# Ultra96toPMODV10.net
KiCad netlist of a schematic drawn in EAGLE
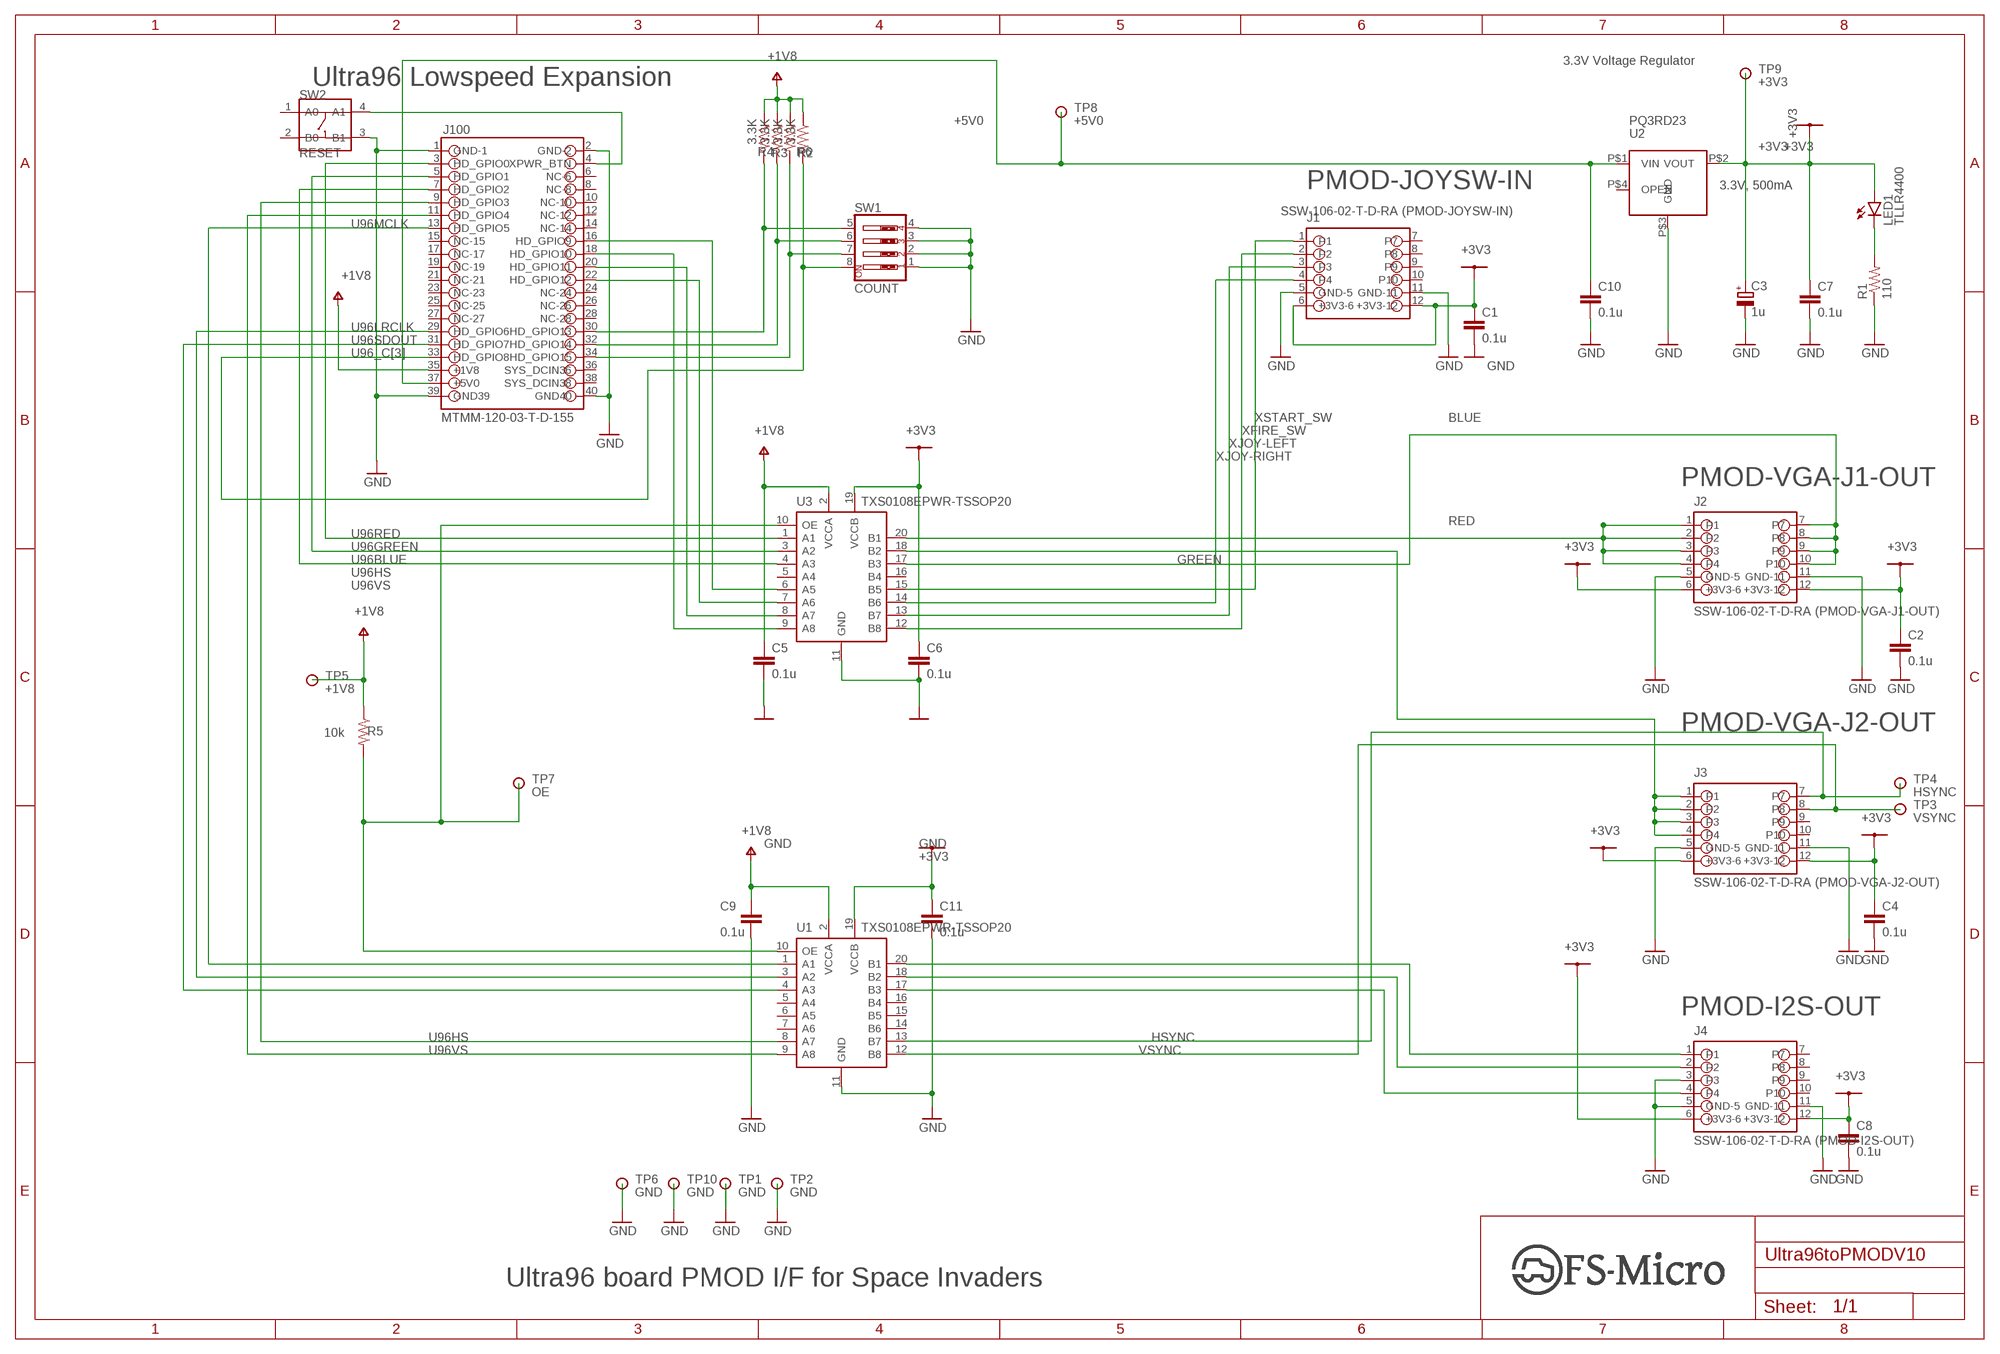
[diagram p0: schematic, sheet 1]

(export (version "E")
  (design (tool "Eeschema 10.0.6"))
  (components
    (comp (ref "C1")
      (value "0.1u")
      (footprint "eagle-import:C050-025X075")
      (libsource (lib "eagle-import") (part "C-EU050-025X075"))
    )
    (comp (ref "C2")
      (value "0.1u")
      (footprint "eagle-import:C050-025X075")
      (libsource (lib "eagle-import") (part "C-EU050-025X075"))
    )
    (comp (ref "C3")
      (value "1u")
      (footprint "eagle-import:E2,5-5")
      (libsource (lib "eagle-import") (part "CPOL-EUE2.5-5"))
    )
    (comp (ref "C4")
      (value "0.1u")
      (footprint "eagle-import:C050-025X075")
      (libsource (lib "eagle-import") (part "C-EU050-025X075"))
    )
    (comp (ref "C5")
      (value "0.1u")
      (footprint "eagle-import:C050-025X075")
      (libsource (lib "eagle-import") (part "C-EU050-025X075"))
    )
    (comp (ref "C6")
      (value "0.1u")
      (footprint "eagle-import:C050-025X075")
      (libsource (lib "eagle-import") (part "C-EU050-025X075"))
    )
    (comp (ref "C7")
      (value "0.1u")
      (footprint "eagle-import:C050-025X075")
      (libsource (lib "eagle-import") (part "C-EU050-025X075"))
    )
    (comp (ref "C8")
      (value "0.1u")
      (footprint "eagle-import:C050-025X075")
      (libsource (lib "eagle-import") (part "C-EU050-025X075"))
    )
    (comp (ref "C9")
      (value "0.1u")
      (footprint "eagle-import:C050-025X075")
      (libsource (lib "eagle-import") (part "C-EU050-025X075"))
    )
    (comp (ref "C10")
      (value "0.1u")
      (footprint "eagle-import:C050-025X075")
      (libsource (lib "eagle-import") (part "C-EU050-025X075"))
    )
    (comp (ref "C11")
      (value "0.1u")
      (footprint "eagle-import:C050-025X075")
      (libsource (lib "eagle-import") (part "C-EU050-025X075"))
    )
    (comp (ref "J1")
      (value "SSW-106-02-T-D-RA (PMOD-JOYSW-IN)")
      (footprint "eagle-import:SSW-106-02-T-D-RA")
      (libsource (lib "eagle-import") (part "SSW-106-02-T-D-RA"))
    )
    (comp (ref "J2")
      (value "SSW-106-02-T-D-RA (PMOD-VGA-J1-OUT)")
      (footprint "eagle-import:SSW-106-02-T-D-RA")
      (libsource (lib "eagle-import") (part "SSW-106-02-T-D-RA"))
    )
    (comp (ref "J3")
      (value "SSW-106-02-T-D-RA (PMOD-VGA-J2-OUT)")
      (footprint "eagle-import:SSW-106-02-T-D-RA")
      (libsource (lib "eagle-import") (part "SSW-106-02-T-D-RA"))
    )
    (comp (ref "J4")
      (value "SSW-106-02-T-D-RA (PMOD-I2S-OUT)")
      (footprint "eagle-import:SSW-106-02-T-D-RA")
      (libsource (lib "eagle-import") (part "SSW-106-02-T-D-RA"))
    )
    (comp (ref "J100")
      (value "MTMM-120-03-T-D-155")
      (footprint "eagle-import:MTMM-120-03-T-D-155")
      (libsource (lib "eagle-import") (part "MTMM-120-03-T-D-155"))
    )
    (comp (ref "LED1")
      (value "TLLR4400")
      (footprint "eagle-import:LED3MM")
      (fields (field (name "MF") "VISHAY SEMICONDUCTOR"))
      (libsource (lib "eagle-import") (part "TLLR4400"))
    )
    (comp (ref "R1")
      (value "110")
      (footprint "eagle-import:0207_10")
      (libsource (lib "eagle-import") (part "R-US_0207/10"))
    )
    (comp (ref "R2")
      (value "3.3K")
      (footprint "eagle-import:0207_10")
      (libsource (lib "eagle-import") (part "R-US_0207/10"))
    )
    (comp (ref "R3")
      (value "3.3K")
      (footprint "eagle-import:0207_10")
      (libsource (lib "eagle-import") (part "R-US_0207/10"))
    )
    (comp (ref "R4")
      (value "3.3K")
      (footprint "eagle-import:0207_10")
      (libsource (lib "eagle-import") (part "R-US_0207/10"))
    )
    (comp (ref "R5")
      (value "10k")
      (footprint "eagle-import:0207_10")
      (libsource (lib "eagle-import") (part "R-US_0207/10"))
    )
    (comp (ref "R6")
      (value "3.3K")
      (footprint "eagle-import:0207_10")
      (libsource (lib "eagle-import") (part "R-US_0207/10"))
    )
    (comp (ref "SW1")
      (value "COUNT")
      (footprint "eagle-import:EDG-04")
      (libsource (lib "eagle-import") (part "SW_DIP-4"))
    )
    (comp (ref "SW2")
      (value "RESET")
      (footprint "eagle-import:SW4-6.0X6.0X5.0MM")
      (libsource (lib "eagle-import") (part "DIP-SWITCH-TACTILE-SPST-NO/TS-1109(4P-D6.0MM)'TS-1109'"))
    )
    (comp (ref "TP1")
      (value "GND")
      (footprint "eagle-import:TP")
      (libsource (lib "eagle-import") (part "TP"))
    )
    (comp (ref "TP2")
      (value "GND")
      (footprint "eagle-import:TP")
      (libsource (lib "eagle-import") (part "TP"))
    )
    (comp (ref "TP3")
      (value "VSYNC")
      (footprint "eagle-import:TP")
      (libsource (lib "eagle-import") (part "TP"))
    )
    (comp (ref "TP4")
      (value "HSYNC")
      (footprint "eagle-import:TP")
      (libsource (lib "eagle-import") (part "TP"))
    )
    (comp (ref "TP5")
      (value "+1V8")
      (footprint "eagle-import:TP")
      (libsource (lib "eagle-import") (part "TP"))
    )
    (comp (ref "TP6")
      (value "GND")
      (footprint "eagle-import:TP")
      (libsource (lib "eagle-import") (part "TP"))
    )
    (comp (ref "TP7") (value "OE") (footprint "eagle-import:TP") (libsource (lib "eagle-import") (part "TP")))
    (comp (ref "TP8")
      (value "+5V0")
      (footprint "eagle-import:TP")
      (libsource (lib "eagle-import") (part "TP"))
    )
    (comp (ref "TP9")
      (value "+3V3")
      (footprint "eagle-import:TP")
      (libsource (lib "eagle-import") (part "TP"))
    )
    (comp (ref "TP10")
      (value "GND")
      (footprint "eagle-import:TP")
      (libsource (lib "eagle-import") (part "TP"))
    )
    (comp (ref "U1")
      (value "TXS0108EPWR-TSSOP20")
      (footprint "eagle-import:TSSOP20-0.65-6.5X4.4MM")
      (fields (field (name "MPN") "TXS0108EPWR"))
      (libsource (lib "eagle-import") (part "LOGIC-TXS0108EPWR(TSSOP20)"))
    )
    (comp (ref "U2")
      (value "PQ3RD23")
      (footprint "eagle-import:PQ3RD23")
      (libsource (lib "eagle-import") (part "PQ3RD23"))
    )
    (comp (ref "U3")
      (value "TXS0108EPWR-TSSOP20")
      (footprint "eagle-import:TSSOP20-0.65-6.5X4.4MM")
      (fields (field (name "MPN") "TXS0108EPWR"))
      (libsource (lib "eagle-import") (part "LOGIC-TXS0108EPWR(TSSOP20)"))
    )
  )
  (nets
    (net (code "1") (name "+1V8") (class "Default")
      (node (ref "C5") (pin "1") (pinfunction "1_1") (pintype "passive"))
      (node (ref "C9") (pin "1") (pinfunction "1_1") (pintype "passive"))
      (node (ref "J100") (pin "35") (pinfunction "+1V8_35") (pintype "passive"))
      (node (ref "R2") (pin "1") (pinfunction "1_1") (pintype "passive"))
      (node (ref "R3") (pin "1") (pinfunction "1_1") (pintype "passive"))
      (node (ref "R4") (pin "1") (pinfunction "1_1") (pintype "passive"))
      (node (ref "R5") (pin "1") (pinfunction "1_1") (pintype "passive"))
      (node (ref "R6") (pin "1") (pinfunction "1_1") (pintype "passive"))
      (node (ref "TP5") (pin "P$1") (pinfunction "P$1_P$1") (pintype "bidirectional"))
      (node (ref "U1") (pin "2") (pinfunction "VCCA_2") (pintype "bidirectional"))
      (node (ref "U3") (pin "2") (pinfunction "VCCA_2") (pintype "bidirectional"))
    )
    (net (code "2") (name "+3V3") (class "Default")
      (node (ref "C1") (pin "1") (pinfunction "1_1") (pintype "passive"))
      (node (ref "C11") (pin "1") (pinfunction "1_1") (pintype "passive"))
      (node (ref "C2") (pin "1") (pinfunction "1_1") (pintype "passive"))
      (node (ref "C3") (pin "+") (pinfunction "+_+") (pintype "passive"))
      (node (ref "C4") (pin "1") (pinfunction "1_1") (pintype "passive"))
      (node (ref "C6") (pin "1") (pinfunction "1_1") (pintype "passive"))
      (node (ref "C7") (pin "1") (pinfunction "1_1") (pintype "passive"))
      (node (ref "C8") (pin "1") (pinfunction "1_1") (pintype "passive"))
      (node (ref "J1") (pin "12") (pinfunction "+3V3-12_12") (pintype "passive"))
      (node (ref "J1") (pin "6") (pinfunction "+3V3-6_6") (pintype "passive"))
      (node (ref "J2") (pin "12") (pinfunction "+3V3-12_12") (pintype "passive"))
      (node (ref "J2") (pin "6") (pinfunction "+3V3-6_6") (pintype "passive"))
      (node (ref "J3") (pin "12") (pinfunction "+3V3-12_12") (pintype "passive"))
      (node (ref "J3") (pin "6") (pinfunction "+3V3-6_6") (pintype "passive"))
      (node (ref "J4") (pin "12") (pinfunction "+3V3-12_12") (pintype "passive"))
      (node (ref "J4") (pin "6") (pinfunction "+3V3-6_6") (pintype "passive"))
      (node (ref "LED1") (pin "A") (pinfunction "A_A") (pintype "passive"))
      (node (ref "TP9") (pin "P$1") (pinfunction "P$1_P$1") (pintype "bidirectional"))
      (node (ref "U1") (pin "19") (pinfunction "VCCB_19") (pintype "bidirectional"))
      (node (ref "U2") (pin "P$2") (pinfunction "VOUT_P$2") (pintype "passive"))
      (node (ref "U3") (pin "19") (pinfunction "VCCB_19") (pintype "bidirectional"))
    )
    (net (code "3") (name "/+5V0") (class "Default")
      (node (ref "C10") (pin "1") (pinfunction "1_1") (pintype "passive"))
      (node (ref "J100") (pin "37") (pinfunction "+5V0_37") (pintype "passive"))
      (node (ref "TP8") (pin "P$1") (pinfunction "P$1_P$1") (pintype "bidirectional"))
      (node (ref "U2") (pin "P$1") (pinfunction "VIN_P$1") (pintype "passive"))
    )
    (net (code "4") (name "/BLUE") (class "Default")
      (node (ref "J2") (pin "10") (pinfunction "P10_10") (pintype "bidirectional"))
      (node (ref "J2") (pin "7") (pinfunction "P7_7") (pintype "bidirectional"))
      (node (ref "J2") (pin "8") (pinfunction "P8_8") (pintype "bidirectional"))
      (node (ref "J2") (pin "9") (pinfunction "P9_9") (pintype "bidirectional"))
      (node (ref "U3") (pin "17") (pinfunction "B3_17") (pintype "bidirectional"))
    )
    (net (code "5") (name "/GREEN") (class "Default")
      (node (ref "J3") (pin "1") (pinfunction "P1_1") (pintype "input"))
      (node (ref "J3") (pin "2") (pinfunction "P2_2") (pintype "bidirectional"))
      (node (ref "J3") (pin "3") (pinfunction "P3_3") (pintype "bidirectional"))
      (node (ref "J3") (pin "4") (pinfunction "P4_4") (pintype "bidirectional"))
      (node (ref "U3") (pin "18") (pinfunction "B2_18") (pintype "bidirectional"))
    )
    (net (code "6") (name "/HSYNC") (class "Default")
      (node (ref "J3") (pin "7") (pinfunction "P7_7") (pintype "bidirectional"))
      (node (ref "TP4") (pin "P$1") (pinfunction "P$1_P$1") (pintype "bidirectional"))
      (node (ref "U1") (pin "13") (pinfunction "B7_13") (pintype "bidirectional"))
    )
    (net (code "7") (name "/RED") (class "Default")
      (node (ref "J2") (pin "1") (pinfunction "P1_1") (pintype "input"))
      (node (ref "J2") (pin "2") (pinfunction "P2_2") (pintype "bidirectional"))
      (node (ref "J2") (pin "3") (pinfunction "P3_3") (pintype "bidirectional"))
      (node (ref "J2") (pin "4") (pinfunction "P4_4") (pintype "bidirectional"))
      (node (ref "U3") (pin "20") (pinfunction "B1_20") (pintype "bidirectional"))
    )
    (net (code "8") (name "/U96BLUE") (class "Default")
      (node (ref "J100") (pin "7") (pinfunction "HD_GPIO2_7") (pintype "bidirectional"))
      (node (ref "U3") (pin "4") (pinfunction "A3_4") (pintype "bidirectional"))
    )
    (net (code "9") (name "/U96GREEN") (class "Default")
      (node (ref "J100") (pin "5") (pinfunction "HD_GPIO1_5") (pintype "bidirectional"))
      (node (ref "U3") (pin "3") (pinfunction "A2_3") (pintype "bidirectional"))
    )
    (net (code "10") (name "/U96HS") (class "Default")
      (node (ref "J100") (pin "9") (pinfunction "HD_GPIO3_9") (pintype "bidirectional"))
      (node (ref "U1") (pin "8") (pinfunction "A7_8") (pintype "bidirectional"))
    )
    (net (code "11") (name "/U96LRCLK") (class "Default")
      (node (ref "J100") (pin "29") (pinfunction "HD_GPIO6_29") (pintype "bidirectional"))
      (node (ref "U1") (pin "3") (pinfunction "A2_3") (pintype "bidirectional"))
    )
    (net (code "12") (name "/U96MCLK") (class "Default")
      (node (ref "J100") (pin "13") (pinfunction "HD_GPIO5_13") (pintype "bidirectional"))
      (node (ref "U1") (pin "1") (pinfunction "A1_1") (pintype "bidirectional"))
    )
    (net (code "13") (name "/U96RED") (class "Default")
      (node (ref "J100") (pin "3") (pinfunction "HD_GPIO0_3") (pintype "bidirectional"))
      (node (ref "U3") (pin "1") (pinfunction "A1_1") (pintype "bidirectional"))
    )
    (net (code "14") (name "/U96SDOUT") (class "Default")
      (node (ref "J100") (pin "31") (pinfunction "HD_GPIO7_31") (pintype "bidirectional"))
      (node (ref "U1") (pin "4") (pinfunction "A3_4") (pintype "bidirectional"))
    )
    (net (code "15") (name "/U96VS") (class "Default")
      (node (ref "J100") (pin "11") (pinfunction "HD_GPIO4_11") (pintype "bidirectional"))
      (node (ref "U1") (pin "9") (pinfunction "A8_9") (pintype "bidirectional"))
    )
    (net (code "16") (name "/U96_C[3]") (class "Default")
      (node (ref "J100") (pin "33") (pinfunction "HD_GPIO8_33") (pintype "bidirectional"))
      (node (ref "R6") (pin "2") (pinfunction "2_2") (pintype "passive"))
      (node (ref "SW1") (pin "8") (pinfunction "8_8") (pintype "passive"))
    )
    (net (code "17") (name "/VSYNC") (class "Default")
      (node (ref "J3") (pin "8") (pinfunction "P8_8") (pintype "bidirectional"))
      (node (ref "TP3") (pin "P$1") (pinfunction "P$1_P$1") (pintype "bidirectional"))
      (node (ref "U1") (pin "12") (pinfunction "B8_12") (pintype "bidirectional"))
    )
    (net (code "18") (name "/XFIRE_SW") (class "Default")
      (node (ref "J1") (pin "2") (pinfunction "P2_2") (pintype "bidirectional"))
      (node (ref "U3") (pin "12") (pinfunction "B8_12") (pintype "bidirectional"))
    )
    (net (code "19") (name "/XJOY-LEFT") (class "Default")
      (node (ref "J1") (pin "3") (pinfunction "P3_3") (pintype "bidirectional"))
      (node (ref "U3") (pin "13") (pinfunction "B7_13") (pintype "bidirectional"))
    )
    (net (code "20") (name "/XJOY-RIGHT") (class "Default")
      (node (ref "J1") (pin "4") (pinfunction "P4_4") (pintype "bidirectional"))
      (node (ref "U3") (pin "14") (pinfunction "B6_14") (pintype "bidirectional"))
    )
    (net (code "21") (name "/XSTART_SW") (class "Default")
      (node (ref "J1") (pin "1") (pinfunction "P1_1") (pintype "input"))
      (node (ref "U3") (pin "15") (pinfunction "B5_15") (pintype "bidirectional"))
    )
    (net (code "22") (name "GND") (class "Default")
      (node (ref "C1") (pin "2") (pinfunction "2_2") (pintype "passive"))
      (node (ref "C10") (pin "2") (pinfunction "2_2") (pintype "passive"))
      (node (ref "C11") (pin "2") (pinfunction "2_2") (pintype "passive"))
      (node (ref "C2") (pin "2") (pinfunction "2_2") (pintype "passive"))
      (node (ref "C3") (pin "-") (pinfunction "-_-") (pintype "passive"))
      (node (ref "C4") (pin "2") (pinfunction "2_2") (pintype "passive"))
      (node (ref "C5") (pin "2") (pinfunction "2_2") (pintype "passive"))
      (node (ref "C6") (pin "2") (pinfunction "2_2") (pintype "passive"))
      (node (ref "C7") (pin "2") (pinfunction "2_2") (pintype "passive"))
      (node (ref "C8") (pin "2") (pinfunction "2_2") (pintype "passive"))
      (node (ref "C9") (pin "2") (pinfunction "2_2") (pintype "passive"))
      (node (ref "J1") (pin "11") (pinfunction "GND-11_11") (pintype "passive"))
      (node (ref "J1") (pin "5") (pinfunction "GND-5_5") (pintype "passive"))
      (node (ref "J100") (pin "1") (pinfunction "GND-1_1") (pintype "passive"))
      (node (ref "J100") (pin "2") (pinfunction "GND-2_2") (pintype "passive"))
      (node (ref "J100") (pin "39") (pinfunction "GND39_39") (pintype "passive"))
      (node (ref "J100") (pin "40") (pinfunction "GND40_40") (pintype "passive"))
      (node (ref "J2") (pin "11") (pinfunction "GND-11_11") (pintype "passive"))
      (node (ref "J2") (pin "5") (pinfunction "GND-5_5") (pintype "passive"))
      (node (ref "J3") (pin "11") (pinfunction "GND-11_11") (pintype "passive"))
      (node (ref "J3") (pin "5") (pinfunction "GND-5_5") (pintype "passive"))
      (node (ref "J4") (pin "11") (pinfunction "GND-11_11") (pintype "passive"))
      (node (ref "J4") (pin "3") (pinfunction "P3_3") (pintype "bidirectional"))
      (node (ref "J4") (pin "5") (pinfunction "GND-5_5") (pintype "passive"))
      (node (ref "R1") (pin "1") (pinfunction "1_1") (pintype "passive"))
      (node (ref "SW1") (pin "1") (pinfunction "1_1") (pintype "passive"))
      (node (ref "SW1") (pin "2") (pinfunction "2_2") (pintype "passive"))
      (node (ref "SW1") (pin "3") (pinfunction "3_3") (pintype "passive"))
      (node (ref "SW1") (pin "4") (pinfunction "4_4") (pintype "passive"))
      (node (ref "SW2") (pin "3") (pinfunction "B1_3") (pintype "bidirectional"))
      (node (ref "TP1") (pin "P$1") (pinfunction "P$1_P$1") (pintype "bidirectional"))
      (node (ref "TP10") (pin "P$1") (pinfunction "P$1_P$1") (pintype "bidirectional"))
      (node (ref "TP2") (pin "P$1") (pinfunction "P$1_P$1") (pintype "bidirectional"))
      (node (ref "TP6") (pin "P$1") (pinfunction "P$1_P$1") (pintype "bidirectional"))
      (node (ref "U1") (pin "11") (pinfunction "GND_11") (pintype "bidirectional"))
      (node (ref "U2") (pin "P$3") (pinfunction "GND_P$3") (pintype "passive"))
      (node (ref "U3") (pin "11") (pinfunction "GND_11") (pintype "bidirectional"))
    )
    (net (code "23") (name "Net-(J4-P1)") (class "Default")
      (node (ref "J4") (pin "1") (pinfunction "P1_1") (pintype "input"))
      (node (ref "U1") (pin "20") (pinfunction "B1_20") (pintype "bidirectional"))
    )
    (net (code "24") (name "Net-(J4-P2)") (class "Default")
      (node (ref "J4") (pin "2") (pinfunction "P2_2") (pintype "bidirectional"))
      (node (ref "U1") (pin "18") (pinfunction "B2_18") (pintype "bidirectional"))
    )
    (net (code "25") (name "Net-(J4-P4)") (class "Default")
      (node (ref "J4") (pin "4") (pinfunction "P4_4") (pintype "bidirectional"))
      (node (ref "U1") (pin "17") (pinfunction "B3_17") (pintype "bidirectional"))
    )
    (net (code "26") (name "Net-(J100-HD_GPIO9)") (class "Default")
      (node (ref "J100") (pin "16") (pinfunction "HD_GPIO9_16") (pintype "bidirectional"))
      (node (ref "U3") (pin "6") (pinfunction "A5_6") (pintype "bidirectional"))
    )
    (net (code "27") (name "Net-(J100-HD_GPIO10)") (class "Default")
      (node (ref "J100") (pin "18") (pinfunction "HD_GPIO10_18") (pintype "bidirectional"))
      (node (ref "U3") (pin "9") (pinfunction "A8_9") (pintype "bidirectional"))
    )
    (net (code "28") (name "Net-(J100-HD_GPIO11)") (class "Default")
      (node (ref "J100") (pin "20") (pinfunction "HD_GPIO11_20") (pintype "bidirectional"))
      (node (ref "U3") (pin "8") (pinfunction "A7_8") (pintype "bidirectional"))
    )
    (net (code "29") (name "Net-(J100-HD_GPIO12)") (class "Default")
      (node (ref "J100") (pin "22") (pinfunction "HD_GPIO12_22") (pintype "bidirectional"))
      (node (ref "U3") (pin "7") (pinfunction "A6_7") (pintype "bidirectional"))
    )
    (net (code "30") (name "Net-(J100-HD_GPIO13)") (class "Default")
      (node (ref "J100") (pin "30") (pinfunction "HD_GPIO13_30") (pintype "bidirectional"))
      (node (ref "R4") (pin "2") (pinfunction "2_2") (pintype "passive"))
      (node (ref "SW1") (pin "5") (pinfunction "5_5") (pintype "passive"))
    )
    (net (code "31") (name "Net-(J100-HD_GPIO14)") (class "Default")
      (node (ref "J100") (pin "32") (pinfunction "HD_GPIO14_32") (pintype "bidirectional"))
      (node (ref "R3") (pin "2") (pinfunction "2_2") (pintype "passive"))
      (node (ref "SW1") (pin "6") (pinfunction "6_6") (pintype "passive"))
    )
    (net (code "32") (name "Net-(J100-HD_GPIO15)") (class "Default")
      (node (ref "J100") (pin "34") (pinfunction "HD_GPIO15_34") (pintype "bidirectional"))
      (node (ref "R2") (pin "2") (pinfunction "2_2") (pintype "passive"))
      (node (ref "SW1") (pin "7") (pinfunction "7_7") (pintype "passive"))
    )
    (net (code "33") (name "Net-(J100-XPWR_BTN)") (class "Default")
      (node (ref "J100") (pin "4") (pinfunction "XPWR_BTN_4") (pintype "bidirectional"))
      (node (ref "SW2") (pin "4") (pinfunction "A1_4") (pintype "bidirectional"))
    )
    (net (code "34") (name "Net-(LED1-C)") (class "Default")
      (node (ref "LED1") (pin "K") (pinfunction "C_K") (pintype "passive"))
      (node (ref "R1") (pin "2") (pinfunction "2_2") (pintype "passive"))
    )
    (net (code "35") (name "Net-(U1-OE)") (class "Default")
      (node (ref "R5") (pin "2") (pinfunction "2_2") (pintype "passive"))
      (node (ref "TP7") (pin "P$1") (pinfunction "P$1_P$1") (pintype "bidirectional"))
      (node (ref "U1") (pin "10") (pinfunction "OE_10") (pintype "bidirectional"))
      (node (ref "U3") (pin "10") (pinfunction "OE_10") (pintype "bidirectional"))
    )
    (net (code "36") (name "unconnected-(J1-P7-Pad7)") (class "Default")
      (node (ref "J1") (pin "7") (pinfunction "P7_7") (pintype "bidirectional"))
    )
    (net (code "37") (name "unconnected-(J1-P8-Pad8)") (class "Default")
      (node (ref "J1") (pin "8") (pinfunction "P8_8") (pintype "bidirectional"))
    )
    (net (code "38") (name "unconnected-(J1-P9-Pad9)") (class "Default")
      (node (ref "J1") (pin "9") (pinfunction "P9_9") (pintype "bidirectional"))
    )
    (net (code "39") (name "unconnected-(J1-P10-Pad10)") (class "Default")
      (node (ref "J1") (pin "10") (pinfunction "P10_10") (pintype "bidirectional"))
    )
    (net (code "40") (name "unconnected-(J3-P9-Pad9)") (class "Default")
      (node (ref "J3") (pin "9") (pinfunction "P9_9") (pintype "bidirectional"))
    )
    (net (code "41") (name "unconnected-(J3-P10-Pad10)") (class "Default")
      (node (ref "J3") (pin "10") (pinfunction "P10_10") (pintype "bidirectional"))
    )
    (net (code "42") (name "unconnected-(J4-P7-Pad7)") (class "Default")
      (node (ref "J4") (pin "7") (pinfunction "P7_7") (pintype "bidirectional"))
    )
    (net (code "43") (name "unconnected-(J4-P8-Pad8)") (class "Default")
      (node (ref "J4") (pin "8") (pinfunction "P8_8") (pintype "bidirectional"))
    )
    (net (code "44") (name "unconnected-(J4-P9-Pad9)") (class "Default")
      (node (ref "J4") (pin "9") (pinfunction "P9_9") (pintype "bidirectional"))
    )
    (net (code "45") (name "unconnected-(J4-P10-Pad10)") (class "Default")
      (node (ref "J4") (pin "10") (pinfunction "P10_10") (pintype "bidirectional"))
    )
    (net (code "46") (name "unconnected-(J100-NC-6-Pad6)") (class "Default")
      (node (ref "J100") (pin "6") (pinfunction "NC-6_6") (pintype "no_connect"))
    )
    (net (code "47") (name "unconnected-(J100-NC-8-Pad8)") (class "Default")
      (node (ref "J100") (pin "8") (pinfunction "NC-8_8") (pintype "no_connect"))
    )
    (net (code "48") (name "unconnected-(J100-NC-10-Pad10)") (class "Default")
      (node (ref "J100") (pin "10") (pinfunction "NC-10_10") (pintype "no_connect"))
    )
    (net (code "49") (name "unconnected-(J100-NC-12-Pad12)") (class "Default")
      (node (ref "J100") (pin "12") (pinfunction "NC-12_12") (pintype "no_connect"))
    )
    (net (code "50") (name "unconnected-(J100-NC-14-Pad14)") (class "Default")
      (node (ref "J100") (pin "14") (pinfunction "NC-14_14") (pintype "no_connect"))
    )
    (net (code "51") (name "unconnected-(J100-NC-15-Pad15)") (class "Default")
      (node (ref "J100") (pin "15") (pinfunction "NC-15_15") (pintype "no_connect"))
    )
    (net (code "52") (name "unconnected-(J100-NC-17-Pad17)") (class "Default")
      (node (ref "J100") (pin "17") (pinfunction "NC-17_17") (pintype "no_connect"))
    )
    (net (code "53") (name "unconnected-(J100-NC-19-Pad19)") (class "Default")
      (node (ref "J100") (pin "19") (pinfunction "NC-19_19") (pintype "no_connect"))
    )
    (net (code "54") (name "unconnected-(J100-NC-21-Pad21)") (class "Default")
      (node (ref "J100") (pin "21") (pinfunction "NC-21_21") (pintype "no_connect"))
    )
    (net (code "55") (name "unconnected-(J100-NC-23-Pad23)") (class "Default")
      (node (ref "J100") (pin "23") (pinfunction "NC-23_23") (pintype "no_connect"))
    )
    (net (code "56") (name "unconnected-(J100-NC-24-Pad24)") (class "Default")
      (node (ref "J100") (pin "24") (pinfunction "NC-24_24") (pintype "no_connect"))
    )
    (net (code "57") (name "unconnected-(J100-NC-25-Pad25)") (class "Default")
      (node (ref "J100") (pin "25") (pinfunction "NC-25_25") (pintype "no_connect"))
    )
    (net (code "58") (name "unconnected-(J100-NC-26-Pad26)") (class "Default")
      (node (ref "J100") (pin "26") (pinfunction "NC-26_26") (pintype "no_connect"))
    )
    (net (code "59") (name "unconnected-(J100-NC-27-Pad27)") (class "Default")
      (node (ref "J100") (pin "27") (pinfunction "NC-27_27") (pintype "no_connect"))
    )
    (net (code "60") (name "unconnected-(J100-NC-28-Pad28)") (class "Default")
      (node (ref "J100") (pin "28") (pinfunction "NC-28_28") (pintype "no_connect"))
    )
    (net (code "61") (name "unconnected-(J100-SYS_DCIN36-Pad36)") (class "Default")
      (node (ref "J100") (pin "36") (pinfunction "SYS_DCIN36_36") (pintype "no_connect"))
    )
    (net (code "62") (name "unconnected-(J100-SYS_DCIN38-Pad38)") (class "Default")
      (node (ref "J100") (pin "38") (pinfunction "SYS_DCIN38_38") (pintype "no_connect"))
    )
    (net (code "63") (name "unconnected-(SW2-A0-Pad1)") (class "Default")
      (node (ref "SW2") (pin "1") (pinfunction "A0_1") (pintype "bidirectional"))
    )
    (net (code "64") (name "unconnected-(SW2-B0-Pad2)") (class "Default")
      (node (ref "SW2") (pin "2") (pinfunction "B0_2") (pintype "bidirectional"))
    )
    (net (code "65") (name "unconnected-(U1-A4-Pad5)") (class "Default")
      (node (ref "U1") (pin "5") (pinfunction "A4_5") (pintype "bidirectional"))
    )
    (net (code "66") (name "unconnected-(U1-A5-Pad6)") (class "Default")
      (node (ref "U1") (pin "6") (pinfunction "A5_6") (pintype "bidirectional"))
    )
    (net (code "67") (name "unconnected-(U1-A6-Pad7)") (class "Default")
      (node (ref "U1") (pin "7") (pinfunction "A6_7") (pintype "bidirectional"))
    )
    (net (code "68") (name "unconnected-(U1-B4-Pad16)") (class "Default")
      (node (ref "U1") (pin "16") (pinfunction "B4_16") (pintype "bidirectional"))
    )
    (net (code "69") (name "unconnected-(U1-B5-Pad15)") (class "Default")
      (node (ref "U1") (pin "15") (pinfunction "B5_15") (pintype "bidirectional"))
    )
    (net (code "70") (name "unconnected-(U1-B6-Pad14)") (class "Default")
      (node (ref "U1") (pin "14") (pinfunction "B6_14") (pintype "bidirectional"))
    )
    (net (code "71") (name "unconnected-(U2-OPEN-PadP$4)") (class "Default")
      (node (ref "U2") (pin "P$4") (pinfunction "OPEN_P$4") (pintype "no_connect"))
    )
    (net (code "72") (name "unconnected-(U3-A4-Pad5)") (class "Default")
      (node (ref "U3") (pin "5") (pinfunction "A4_5") (pintype "bidirectional"))
    )
    (net (code "73") (name "unconnected-(U3-B4-Pad16)") (class "Default")
      (node (ref "U3") (pin "16") (pinfunction "B4_16") (pintype "bidirectional"))
    )
  )
)
